# EFR32G13_POWER_RESET.net
KiCad netlist of a schematic drawn in Altium Designer
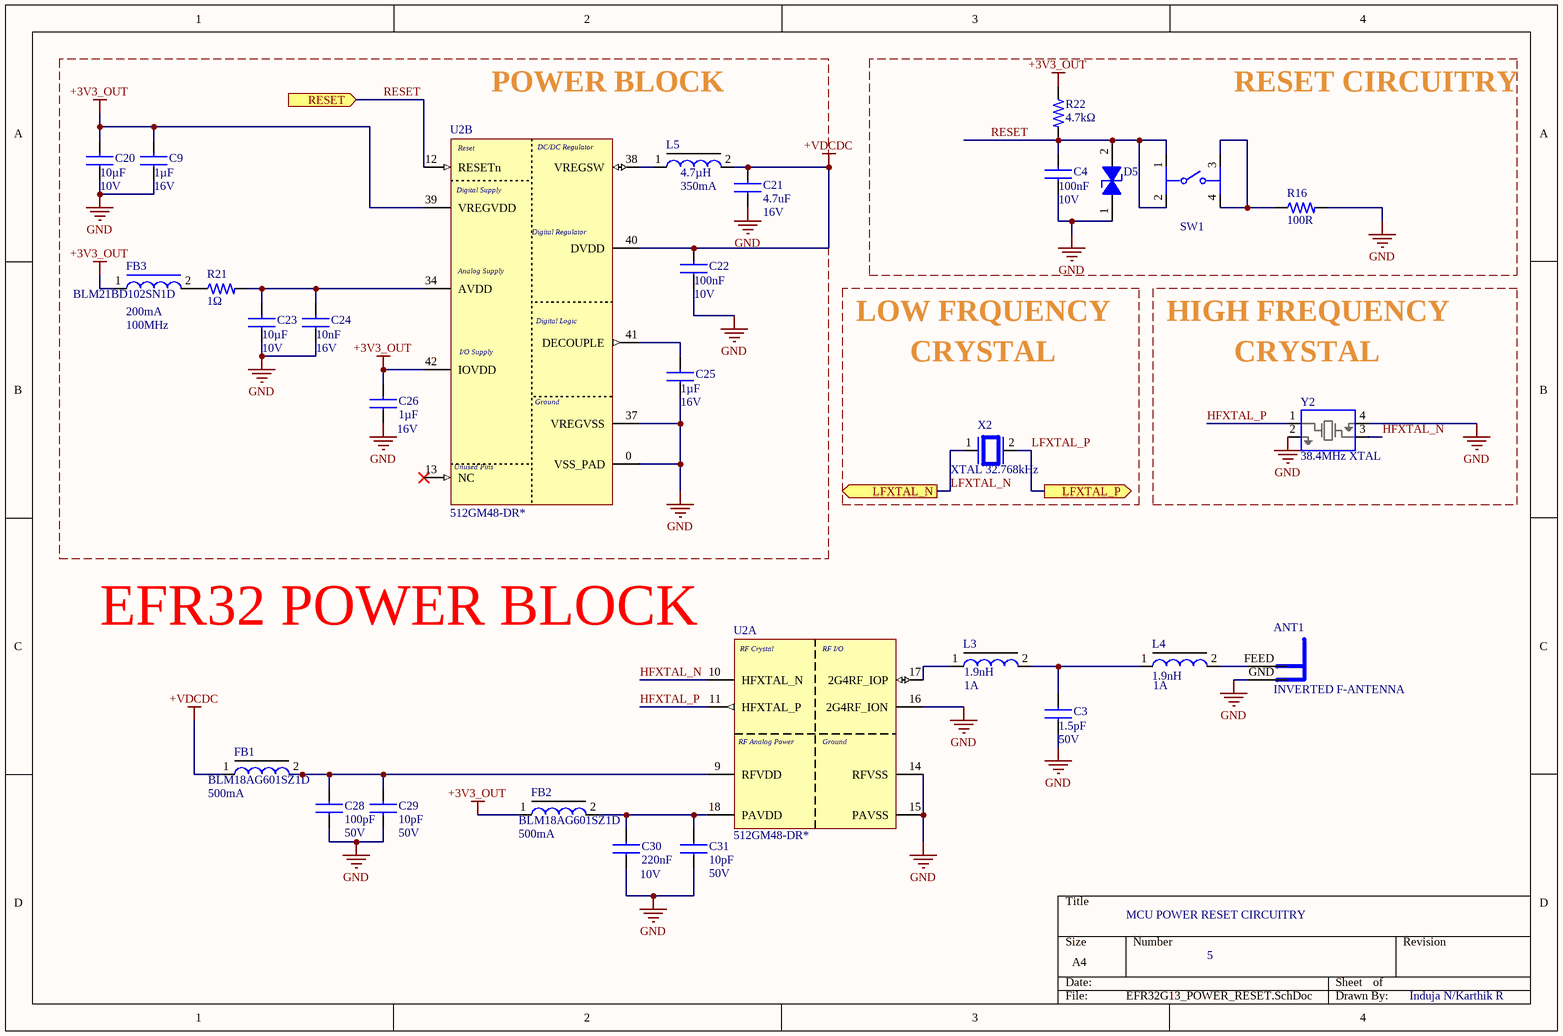
[diagram p0: EFR32G13_POWER_RESET.SchDoc]

(export (version "E")
  (design (tool "Eeschema 10.0.6"))
  (components
    (comp (ref "ANT1")
      (value "INVERTED F-ANTENNA")
      (footprint "F_ANTENNA")
      (libsource (lib "LPEDT_Components") (part "INVERTED F-ANTENNA"))
    )
    (comp (ref "C3")
      (value "1.5pF")
      (footprint "Capacitor 0402")
      (fields
        (field (name "MANUFACTURER") "Murata")
        (field (name "MANUFACTURER PART NUMBER") "GJM1555C1H1R5WB01D")
        (field (name "RATED DC VOLTAGE (URDC)") "50V")
        (field (name "Comment") "CAP 1.5pF 50V 0402")
      )
      (libsource (lib "LPEDT_Components") (part "CAP 1.5pF 50V 0402"))
    )
    (comp (ref "C4")
      (value "100nF")
      (footprint "CAP_0603_1MM")
      (description "0603 0.1 uF 10 V ±10% Tolerance X7R SMT Multilayer Ceramic Chip Capacitor")
      (fields
        (field (name "MANUFACTURER") "Vishay")
        (field (name "MANUFACTURER PART NUMBER") "VJ0603Y104KXQCW1BC")
        (field (name "VOLTAGE RATING (DC)") "10V")
      )
      (libsource (lib "LPEDT_Components") (part "CAP 0.1uF 0603"))
    )
    (comp (ref "C9")
      (value "1µF")
      (footprint "Capacitor 0603")
      (description "16V 1uF X7R ±10% 0603 Multilayer Ceramic Capacitors MLCC - SMD/SMT ROHS")
      (fields
        (field (name "MANUFACTURER") "Samsung Electro-Mechanics")
        (field (name "MANUFACTURER PART NUMBER") "CL10B105KO8NNNC")
        (field (name "VOLTAGE") "16V")
      )
      (libsource (lib "LPEDT_Components") (part "CAP 1uF 0603"))
    )
    (comp (ref "C20")
      (value "10µF")
      (footprint "CAP_0603_1MM")
      (description "10V 10uF X7R ±10% 0603 Multilayer Ceramic Capacitors MLCC - SMD/SMT ROHS")
      (fields
        (field (name "MANUFACTURER") "Murata")
        (field (name "MANUFACTURER PART NUMBER") "GRM188Z71A106KA73D")
        (field (name "VOLTAGE RATING") "10V")
      )
      (libsource (lib "LPEDT_Components") (part "CAP 10uF 0603"))
    )
    (comp (ref "C21")
      (value "16V")
      (footprint "CAPC1608X90N")
      (description "4.7 ÂµF Â±10% 16V Ceramic Capacitor X5R 0603 (1608 Metric)")
      (fields
        (field (name "MF") "Samsung Electro-Mechanics")
        (field (name "MP") "CL10A475KO8NNNC")
        (field (name "ALTIUM_VALUE") "4.7uF")
      )
      (libsource (lib "LPEDT_Components") (part "CAP 4.7uF 16V 0603"))
    )
    (comp (ref "C22")
      (value "100nF")
      (footprint "CAP_0603_1MM")
      (description "0603 0.1 uF 10 V ±10% Tolerance X7R SMT Multilayer Ceramic Chip Capacitor")
      (fields
        (field (name "MANUFACTURER") "Vishay")
        (field (name "MANUFACTURER PART NUMBER") "VJ0603Y104KXQCW1BC")
        (field (name "VOLTAGE RATING (DC)") "10V")
      )
      (libsource (lib "LPEDT_Components") (part "CAP 0.1uF 0603"))
    )
    (comp (ref "C23")
      (value "10µF")
      (footprint "CAP_0603_1MM")
      (description "10V 10uF X7R ±10% 0603 Multilayer Ceramic Capacitors MLCC - SMD/SMT ROHS")
      (fields
        (field (name "MANUFACTURER") "Murata")
        (field (name "MANUFACTURER PART NUMBER") "GRM188Z71A106KA73D")
        (field (name "VOLTAGE RATING") "10V")
      )
      (libsource (lib "LPEDT_Components") (part "CAP 10uF 0603"))
    )
    (comp (ref "C24")
      (value "10nF")
      (footprint "Capacitor 0603")
      (description "Multilayer Ceramic Capacitors MLCC - SMD/SMT 16V 0.01uF X7R 0603 10% AEC-Q200")
      (fields
        (field (name "MANUFACTURER") "KEMET")
        (field (name "MANUFACTURER PART NUMBER") "C0603C103K4RECAUTO")
        (field (name "VOLTAGE RATING (DC)") "16V")
      )
      (libsource (lib "LPEDT_Components") (part "CAP 10nF 0603"))
    )
    (comp (ref "C25")
      (value "1µF")
      (footprint "Capacitor 0603")
      (description "16V 1uF X7R ±10% 0603 Multilayer Ceramic Capacitors MLCC - SMD/SMT ROHS")
      (fields
        (field (name "MANUFACTURER") "Samsung Electro-Mechanics")
        (field (name "MANUFACTURER PART NUMBER") "CL10B105KO8NNNC")
        (field (name "VOLTAGE RATING (DC)") "16V")
      )
      (libsource (lib "LPEDT_Components") (part "CAP 1uF 0603"))
    )
    (comp (ref "C26")
      (value "1µF")
      (footprint "Capacitor 0603")
      (description "16V 1uF X7R ±10% 0603 Multilayer Ceramic Capacitors MLCC - SMD/SMT ROHS")
      (fields
        (field (name "MANUFACTURER") "Samsung Electro-Mechanics")
        (field (name "MANUFACTURER PART NUMBER") "CL10B105KO8NNNC")
        (field (name "VOLTAGE") "16V")
      )
      (libsource (lib "LPEDT_Components") (part "CAP 1uF 0603"))
    )
    (comp (ref "C28")
      (value "100pF")
      (footprint "CAP_0603_1MM")
      (description "50V 100pF NP0 ±5% 0603 Multilayer Ceramic Capacitors MLCC - SMD/SMT ROHS")
      (fields
        (field (name "MANUFACTURER") "Yageo Group")
        (field (name "MANUFACTURER PART NUMBER") "CC0603JRNPO9BN101")
        (field (name "VOLTAGE RATING (DC)") "50V")
      )
      (libsource (lib "LPEDT_Components") (part "CAP 100pF 0603"))
    )
    (comp (ref "C29")
      (value "10pF")
      (footprint "Capacitor 0603")
      (fields
        (field (name "MANUFACTURER") "Murata")
        (field (name "MANUFACTURER PART NUMBER") "GRM1555C1H100FA01D")
        (field (name "RATED DC VOLTAGE (URDC)") "50V")
        (field (name "Comment") "CAP 10pF 50V 0603")
      )
      (libsource (lib "LPEDT_Components") (part "CAP 10pF 50V 0603"))
    )
    (comp (ref "C30")
      (value "220nF")
      (footprint "Capacitor 0603")
      (description "0603 0.22 uF 10 V ±10% Tolerance X7R SMT Multilayer Ceramic Capacitor")
      (fields
        (field (name "MANUFACTURER") "Murata")
        (field (name "MANUFACTURER PART NUMBER") "GRM188R71A224KA01J")
        (field (name "VOLTAGE RATING") "10V")
      )
      (libsource (lib "LPEDT_Components") (part "CAP 220nF 10V 0603"))
    )
    (comp (ref "C31")
      (value "10pF")
      (footprint "Capacitor 0603")
      (fields
        (field (name "MANUFACTURER") "Murata")
        (field (name "MANUFACTURER PART NUMBER") "GRM1555C1H100FA01D")
        (field (name "RATED DC VOLTAGE (URDC)") "50V")
        (field (name "Comment") "CAP 10pF 50V 0603")
      )
      (libsource (lib "LPEDT_Components") (part "CAP 10pF 50V 0603"))
    )
    (comp (ref "D5")
      (value "824032815")
      (footprint "WE-TVS_DFN1610-2L")
      (description "824032815 Tvs Diode, Bidir, 5V, Dfn1610 Rohs Compliant: Yes ¦Wurth Elektronik 824032815")
      (libsource (lib "LPEDT_Components") (part "TVS Diode ESD Protection"))
    )
    (comp (ref "FB1")
      (value "BLM18AG601SZ1D")
      (footprint "Ferrite 0603")
      (description "Chip Ferrite Bead, 0603, 600Ω @ 100MHz, 0.38Ω, 25%, 500mA CMP-06046-002436-1")
      (fields (field (name "MAX CURRENT RATING") "500mA"))
      (libsource (lib "LPEDT_Components") (part "600R Ferrite bead"))
    )
    (comp (ref "FB2")
      (value "BLM18AG601SZ1D")
      (footprint "Ferrite 0603")
      (description "Chip Ferrite Bead, 0603, 600Ω @ 100MHz, 0.38Ω, 25%, 500mA CMP-06046-002436-1")
      (fields (field (name "MAX CURRENT RATING") "500mA"))
      (libsource (lib "LPEDT_Components") (part "600R Ferrite bead"))
    )
    (comp (ref "FB3")
      (value "BLM21BD102SN1D")
      (footprint "FP-BLM21-0_2-t0_85-e0_5-IPC_A")
      (description "Ferrite Beads Multi-Layer 1KOhm 25% 100MHz 250mA 400mOhm DCR 0805 T/R")
      (fields
        (field (name "MANUFACTURER") "Murata")
        (field (name "CURRENT RATING") "200mA")
        (field (name "TEST FREQUENCY") "100MHz")
        (field (name "TOLERANCE") "25%")
      )
      (libsource (lib "LPEDT_Components") (part "BLM21BD102SN1D"))
    )
    (comp (ref "L3")
      (value "1.9nH")
      (footprint "Ferrite 0402")
      (description "Inductor, 1.9Nh, 8Ghz, 0402 Rohs Compliant: Yes ¦Murata LQG15WZ1N9S02D")
      (fields
        (field (name "MANUFACTURER") "Murata")
        (field (name "MANUFACTURER PART NUMBER") "LQG15WZ1N9S02D")
        (field (name "CURRENT RATING") "1A")
      )
      (libsource (lib "LPEDT_Components") (part "IND 1.9nH"))
    )
    (comp (ref "L4")
      (value "1.9nH")
      (footprint "Ferrite 0402")
      (description "Inductor, 1.9Nh, 8Ghz, 0402 Rohs Compliant: Yes ¦Murata LQG15WZ1N9S02D")
      (fields
        (field (name "MANUFACTURER") "Murata")
        (field (name "MANUFACTURER PART NUMBER") "LQG15WZ1N9S02D")
        (field (name "CURRENT RATING") "1A")
      )
      (libsource (lib "LPEDT_Components") (part "IND 1.9nH"))
    )
    (comp (ref "L5")
      (value "4.7µH")
      (footprint "Capacitor 0603")
      (description "Inductor Power Shielded Multi-Layer 4.7uH 20% 2MHz Ferrite 0.12A 0.65Ohm DCR 0603 T/R")
      (fields
        (field (name "MANUFACTURER") "TDK")
        (field (name "MANUFACTURER PART NUMBER") "MLZ1608M4R7WT000")
        (field (name "MAX CURRENT RATING") "350mA")
      )
      (libsource (lib "LPEDT_Components") (part "IND 4.7uH"))
    )
    (comp (ref "R16")
      (value "100R")
      (footprint "RES_0603_1608X06")
      (fields
        (field (name "MANUFACTURER") "Yageo")
        (field (name "MANUFACTURER PART NUMBER") "RC0603FR-07100RL")
        (field (name "TOLERANCE") "1%")
      )
      (libsource (lib "LPEDT_Components") (part "RES 100R 0603"))
    )
    (comp (ref "R21")
      (value "1Ω")
      (footprint "RES_0603_1608X06")
      (fields
        (field (name "MANUFACTURER") "Yageo")
        (field (name "MANUFACTURER PART NUMBER") "RC0603FR-074K7L")
        (field (name "TOLERANCE") "1%")
      )
      (libsource (lib "LPEDT_Components") (part "RES 1Ohm 0603"))
    )
    (comp (ref "R22")
      (value "4.7kΩ")
      (footprint "RES_0603_1608X06")
      (fields
        (field (name "MANUFACTURER") "Yageo")
        (field (name "MANUFACTURER PART NUMBER") "RC0603FR-074K7L")
        (field (name "TOLERANCE") "1%")
      )
      (libsource (lib "LPEDT_Components") (part "RES 4.7K 0603"))
    )
    (comp (ref "SW1")
      (value "~")
      (footprint "SWITCH")
      (description "Switch Tactile SPST N.O. 0.05A 12VDC 200000Cycles Gull Wing Surface Mount T/R")
      (fields
        (field (name "MANUFACTURER") "C&K Components")
        (field (name "MANUFACTURER PART NUMBER") "PTS526 SK15 SMTR2 LFS")
      )
      (libsource (lib "LPEDT_Components") (part "PTS526 SK15 SMTR2 LFS"))
    )
    (comp (ref "U2")
      (value "512GM48-DR*")
      (footprint "QFN_48_7x7")
      (description "Blue Gecko QFN48 2.4 G 19 dB BLE/Proprietary 512 kB 64 kB(RAM) 31GPIO")
      (fields
        (field (name "MANUFACTURER") "Silicon Labs")
        (field (name "MANUFACTURER PART NUMBER") "EFR32BG13P732F512GM48-DR")
      )
      (libsource (lib "LPEDT_Components") (part "EFR32BG13P732F512GM48-DR"))
    )
    (comp (ref "X2")
      (value "XTAL 32.768kHz")
      (footprint "XTAL_32.768KHZ-T")
      (description "Crystal 0.032768MHz ±20ppm (Tol) 12.5pF Flexural 70000Ohm 2-Pin CSMD T/R")
      (fields
        (field (name "MANUFACTURER") "Abracon")
        (field (name "MANUFACTURER PART NUMBER") "ABS07-32.768KHZ-H-T")
      )
      (libsource (lib "LPEDT_Components") (part "XTAL 32.768kHz"))
    )
    (comp (ref "Y2")
      (value "38.4MHz XTAL")
      (footprint "XTAL 38.4MHz")
      (description "Fundamental Active RoHS Compliant MHz Crystal Crystal 10pF 0.022 0.55mm -20C~70C 80Ohm")
      (fields (field (name "MANUFACTURER") "TXC") (field (name "MANUFACTURER PART NUMBER") "8Y38472012"))
      (libsource (lib "LPEDT_Components") (part "38.4MHz XTAL"))
    )
  )
  (nets
    (net (code "1") (name "+3V3_OUT") (class "Default")
      (node (ref "C20") (pin "1") (pinfunction "1_1") (pintype "passive"))
      (node (ref "C26") (pin "1") (pinfunction "1_1") (pintype "passive"))
      (node (ref "C9") (pin "1") (pinfunction "1_1") (pintype "passive"))
      (node (ref "FB2") (pin "1") (pinfunction "1_1") (pintype "passive"))
      (node (ref "FB3") (pin "1") (pinfunction "1_1") (pintype "passive"))
      (node (ref "R22") (pin "1") (pinfunction "1_1") (pintype "passive"))
      (node (ref "U2") (pin "39") (pinfunction "VREGVDD_39") (pintype "power_in"))
      (node (ref "U2") (pin "42") (pinfunction "IOVDD_42") (pintype "power_in"))
    )
    (net (code "2") (name "+VDCDC") (class "Default")
      (node (ref "C21") (pin "1") (pinfunction "1_1") (pintype "passive"))
      (node (ref "C22") (pin "1") (pinfunction "1_1") (pintype "passive"))
      (node (ref "FB1") (pin "1") (pinfunction "1_1") (pintype "passive"))
      (node (ref "L5") (pin "2") (pinfunction "2_2") (pintype "passive"))
      (node (ref "U2") (pin "40") (pinfunction "DVDD_40") (pintype "power_in"))
    )
    (net (code "3") (name "/HFXTAL_N") (class "Default")
      (node (ref "U2") (pin "10") (pinfunction "HFXTAL_N_10") (pintype "input"))
      (node (ref "Y2") (pin "3") (pinfunction "3_3") (pintype "passive"))
    )
    (net (code "4") (name "/HFXTAL_P") (class "Default")
      (node (ref "U2") (pin "11") (pinfunction "HFXTAL_P_11") (pintype "output"))
      (node (ref "Y2") (pin "1") (pinfunction "1_1") (pintype "passive"))
    )
    (net (code "5") (name "/LFXTAL_N") (class "Default")
      (node (ref "X2") (pin "1") (pinfunction "1_1") (pintype "passive"))
    )
    (net (code "6") (name "/LFXTAL_P") (class "Default")
      (node (ref "X2") (pin "2") (pinfunction "2_2") (pintype "passive"))
    )
    (net (code "7") (name "/RESET") (class "Default")
      (node (ref "C4") (pin "1") (pinfunction "1_1") (pintype "passive"))
      (node (ref "D5") (pin "2") (pinfunction "GND_2") (pintype "passive"))
      (node (ref "R22") (pin "2") (pinfunction "2_2") (pintype "passive"))
      (node (ref "SW1") (pin "1") (pinfunction "1_1") (pintype "passive"))
      (node (ref "SW1") (pin "2") (pinfunction "2_2") (pintype "passive"))
      (node (ref "U2") (pin "12") (pinfunction "RESETn_12") (pintype "input"))
    )
    (net (code "8") (name "GND") (class "Default")
      (node (ref "ANT1") (pin "GND") (pinfunction "GND_GND") (pintype "power_in"))
      (node (ref "C20") (pin "2") (pinfunction "2_2") (pintype "passive"))
      (node (ref "C21") (pin "2") (pinfunction "2_2") (pintype "passive"))
      (node (ref "C22") (pin "2") (pinfunction "2_2") (pintype "passive"))
      (node (ref "C23") (pin "2") (pinfunction "2_2") (pintype "passive"))
      (node (ref "C24") (pin "2") (pinfunction "2_2") (pintype "passive"))
      (node (ref "C25") (pin "2") (pinfunction "2_2") (pintype "passive"))
      (node (ref "C26") (pin "2") (pinfunction "2_2") (pintype "passive"))
      (node (ref "C28") (pin "2") (pinfunction "2_2") (pintype "passive"))
      (node (ref "C29") (pin "2") (pinfunction "2_2") (pintype "passive"))
      (node (ref "C3") (pin "2") (pinfunction "2_2") (pintype "passive"))
      (node (ref "C30") (pin "2") (pinfunction "2_2") (pintype "passive"))
      (node (ref "C31") (pin "2") (pinfunction "2_2") (pintype "passive"))
      (node (ref "C4") (pin "2") (pinfunction "2_2") (pintype "passive"))
      (node (ref "C9") (pin "2") (pinfunction "2_2") (pintype "passive"))
      (node (ref "D5") (pin "1") (pinfunction "I/O_1_1") (pintype "passive"))
      (node (ref "R16") (pin "2") (pinfunction "2_2") (pintype "passive"))
      (node (ref "U2") (pin "0") (pinfunction "VSS_PAD_0") (pintype "power_in"))
      (node (ref "U2") (pin "14") (pinfunction "RFVSS_14") (pintype "power_in"))
      (node (ref "U2") (pin "15") (pinfunction "PAVSS_15") (pintype "power_in"))
      (node (ref "U2") (pin "16") (pinfunction "2G4RF_ION_16") (pintype "bidirectional"))
      (node (ref "U2") (pin "37") (pinfunction "VREGVSS_37") (pintype "power_in"))
      (node (ref "Y2") (pin "2") (pinfunction "2_2") (pintype "passive"))
      (node (ref "Y2") (pin "4") (pinfunction "4_4") (pintype "passive"))
    )
    (net (code "9") (name "Net-(ANT1-PadFEED)") (class "Default")
      (node (ref "ANT1") (pin "FEED") (pinfunction "FEED_FEED") (pintype "passive"))
      (node (ref "L4") (pin "2") (pinfunction "2_2") (pintype "passive"))
    )
    (net (code "10") (name "Net-(C3-Pad1)") (class "Default")
      (node (ref "C3") (pin "1") (pinfunction "1_1") (pintype "passive"))
      (node (ref "L3") (pin "2") (pinfunction "2_2") (pintype "passive"))
      (node (ref "L4") (pin "1") (pinfunction "1_1") (pintype "passive"))
    )
    (net (code "11") (name "Net-(FB3-Pad2)") (class "Default")
      (node (ref "FB3") (pin "2") (pinfunction "2_2") (pintype "passive"))
      (node (ref "R21") (pin "1") (pinfunction "1_1") (pintype "passive"))
    )
    (net (code "12") (name "Net-(R16-Pad1)") (class "Default")
      (node (ref "R16") (pin "1") (pinfunction "1_1") (pintype "passive"))
      (node (ref "SW1") (pin "3") (pinfunction "3_3") (pintype "passive"))
      (node (ref "SW1") (pin "4") (pinfunction "4_4") (pintype "passive"))
    )
    (net (code "13") (name "Net-(U2A-2G4RF_IOP)") (class "Default")
      (node (ref "L3") (pin "1") (pinfunction "1_1") (pintype "passive"))
      (node (ref "U2") (pin "17") (pinfunction "2G4RF_IOP_17") (pintype "bidirectional"))
    )
    (net (code "14") (name "Net-(U2A-PAVDD)") (class "Default")
      (node (ref "C30") (pin "1") (pinfunction "1_1") (pintype "passive"))
      (node (ref "C31") (pin "1") (pinfunction "1_1") (pintype "passive"))
      (node (ref "FB2") (pin "2") (pinfunction "2_2") (pintype "passive"))
      (node (ref "U2") (pin "18") (pinfunction "PAVDD_18") (pintype "power_in"))
    )
    (net (code "15") (name "Net-(U2A-RFVDD)") (class "Default")
      (node (ref "C28") (pin "1") (pinfunction "1_1") (pintype "passive"))
      (node (ref "C29") (pin "1") (pinfunction "1_1") (pintype "passive"))
      (node (ref "FB1") (pin "2") (pinfunction "2_2") (pintype "passive"))
      (node (ref "U2") (pin "9") (pinfunction "RFVDD_9") (pintype "power_in"))
    )
    (net (code "16") (name "Net-(U2B-AVDD)") (class "Default")
      (node (ref "C23") (pin "1") (pinfunction "1_1") (pintype "passive"))
      (node (ref "C24") (pin "1") (pinfunction "1_1") (pintype "passive"))
      (node (ref "R21") (pin "2") (pinfunction "2_2") (pintype "passive"))
      (node (ref "U2") (pin "34") (pinfunction "AVDD_34") (pintype "power_in"))
    )
    (net (code "17") (name "Net-(U2B-DECOUPLE)") (class "Default")
      (node (ref "C25") (pin "1") (pinfunction "1_1") (pintype "passive"))
      (node (ref "U2") (pin "41") (pinfunction "DECOUPLE_41") (pintype "output"))
    )
    (net (code "18") (name "Net-(U2B-VREGSW)") (class "Default")
      (node (ref "L5") (pin "1") (pinfunction "1_1") (pintype "passive"))
      (node (ref "U2") (pin "38") (pinfunction "VREGSW_38") (pintype "bidirectional"))
    )
    (net (code "19") (name "unconnected-(U2B-NC-Pad13)") (class "Default")
      (node (ref "U2") (pin "13") (pinfunction "NC_13") (pintype "input+no_connect"))
    )
  )
)
